# matrix4x4-b.net
KiCad netlist of a schematic drawn in EAGLE
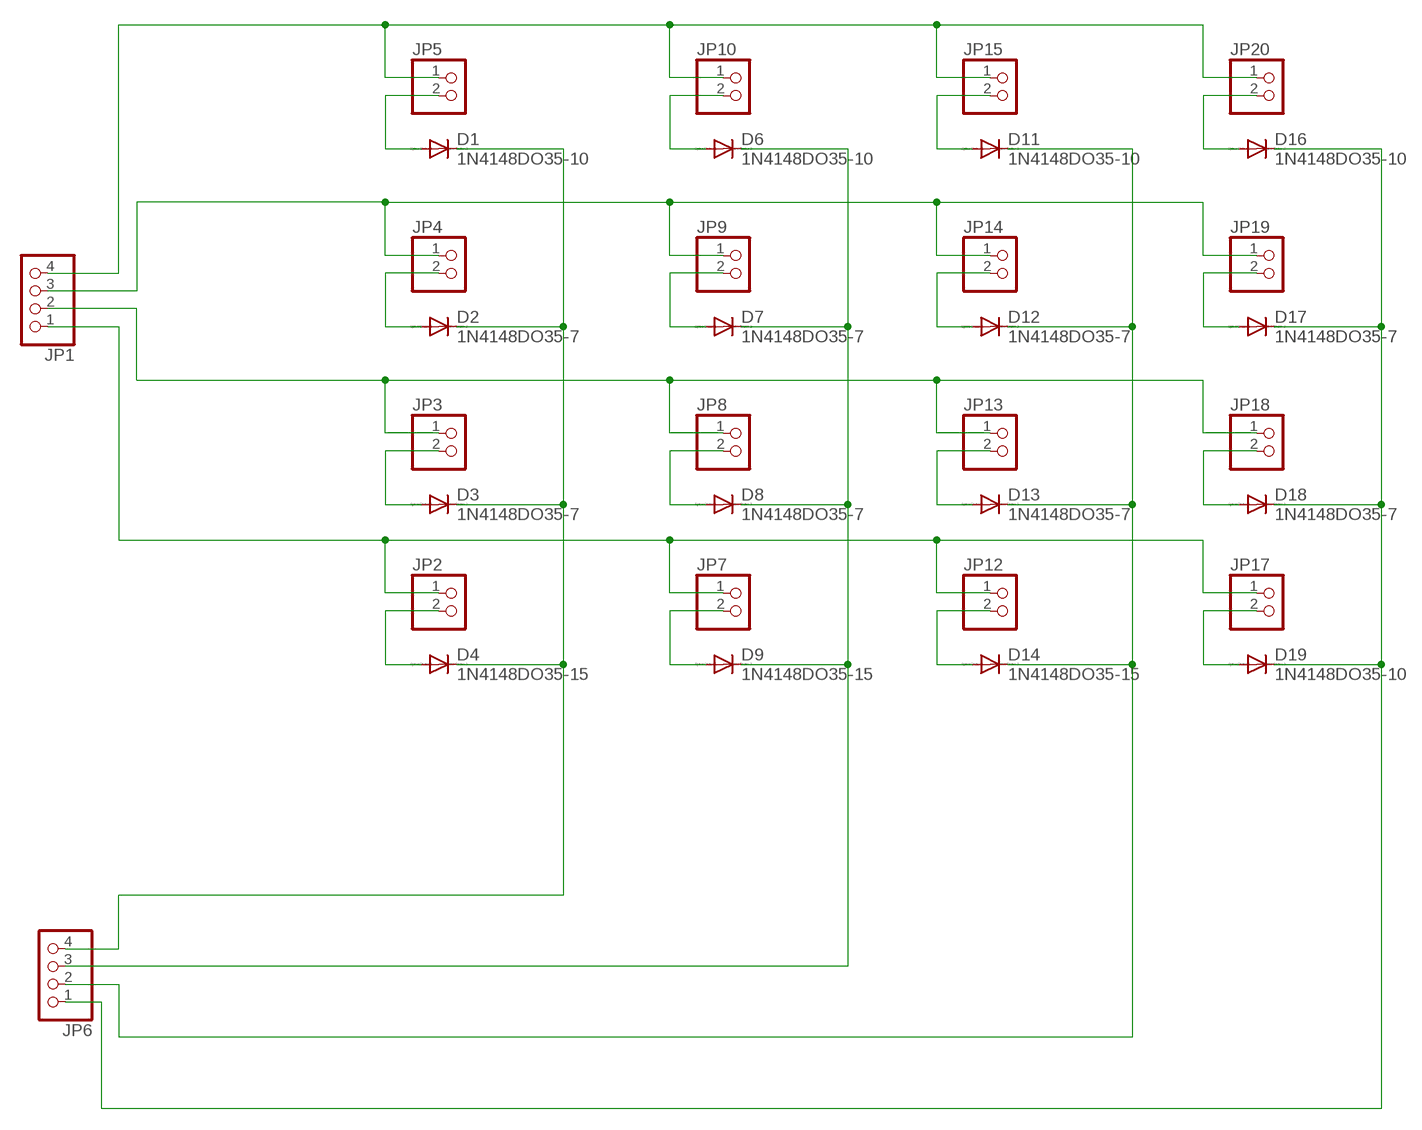
[diagram p0: schematic, sheet 1]

(export (version "E")
  (design (tool "Eeschema 10.0.6"))
  (components
    (comp (ref "D1")
      (value "1N4148DO35-10")
      (footprint "eagle-import:DO35-10")
      (libsource (lib "eagle-import") (part "diode_1N4148DO35-10"))
    )
    (comp (ref "D2")
      (value "1N4148DO35-7")
      (footprint "eagle-import:DO35-7")
      (libsource (lib "eagle-import") (part "diode_1N4148DO35-7"))
    )
    (comp (ref "D3")
      (value "1N4148DO35-7")
      (footprint "eagle-import:DO35-7")
      (libsource (lib "eagle-import") (part "diode_1N4148DO35-7"))
    )
    (comp (ref "D4")
      (value "1N4148DO35-15")
      (footprint "eagle-import:DO35-10")
      (libsource (lib "eagle-import") (part "1N4148DO35-15"))
    )
    (comp (ref "D6")
      (value "1N4148DO35-10")
      (footprint "eagle-import:DO35-10")
      (libsource (lib "eagle-import") (part "diode_1N4148DO35-10"))
    )
    (comp (ref "D7")
      (value "1N4148DO35-7")
      (footprint "eagle-import:DO35-7")
      (libsource (lib "eagle-import") (part "diode_1N4148DO35-7"))
    )
    (comp (ref "D8")
      (value "1N4148DO35-7")
      (footprint "eagle-import:DO35-7")
      (libsource (lib "eagle-import") (part "diode_1N4148DO35-7"))
    )
    (comp (ref "D9")
      (value "1N4148DO35-15")
      (footprint "eagle-import:DO35-10")
      (libsource (lib "eagle-import") (part "1N4148DO35-15"))
    )
    (comp (ref "D11")
      (value "1N4148DO35-10")
      (footprint "eagle-import:DO35-10")
      (libsource (lib "eagle-import") (part "diode_1N4148DO35-10"))
    )
    (comp (ref "D12")
      (value "1N4148DO35-7")
      (footprint "eagle-import:DO35-7")
      (libsource (lib "eagle-import") (part "diode_1N4148DO35-7"))
    )
    (comp (ref "D13")
      (value "1N4148DO35-7")
      (footprint "eagle-import:DO35-7")
      (libsource (lib "eagle-import") (part "diode_1N4148DO35-7"))
    )
    (comp (ref "D14")
      (value "1N4148DO35-15")
      (footprint "eagle-import:DO35-10")
      (libsource (lib "eagle-import") (part "1N4148DO35-15"))
    )
    (comp (ref "D16")
      (value "1N4148DO35-10")
      (footprint "eagle-import:DO35-10")
      (libsource (lib "eagle-import") (part "diode_1N4148DO35-10"))
    )
    (comp (ref "D17")
      (value "1N4148DO35-7")
      (footprint "eagle-import:DO35-7")
      (libsource (lib "eagle-import") (part "diode_1N4148DO35-7"))
    )
    (comp (ref "D18")
      (value "1N4148DO35-7")
      (footprint "eagle-import:DO35-7")
      (libsource (lib "eagle-import") (part "diode_1N4148DO35-7"))
    )
    (comp (ref "D19")
      (value "1N4148DO35-10")
      (footprint "eagle-import:DO35-10")
      (libsource (lib "eagle-import") (part "diode_1N4148DO35-10"))
    )
    (comp (ref "JP1")
      (value "PINHD-1X4")
      (footprint "eagle-import:1X04")
      (libsource (lib "eagle-import") (part "PINHD-1X4"))
    )
    (comp (ref "JP2")
      (value "PINHD-1X2")
      (footprint "eagle-import:1X02")
      (libsource (lib "eagle-import") (part "PINHD-1X2"))
    )
    (comp (ref "JP3")
      (value "PINHD-1X2")
      (footprint "eagle-import:1X02")
      (libsource (lib "eagle-import") (part "PINHD-1X2"))
    )
    (comp (ref "JP4")
      (value "PINHD-1X2")
      (footprint "eagle-import:1X02")
      (libsource (lib "eagle-import") (part "PINHD-1X2"))
    )
    (comp (ref "JP5")
      (value "PINHD-1X2")
      (footprint "eagle-import:1X02")
      (libsource (lib "eagle-import") (part "PINHD-1X2"))
    )
    (comp (ref "JP6")
      (value "PINHD-1X4")
      (footprint "eagle-import:1X04")
      (libsource (lib "eagle-import") (part "PINHD-1X4"))
    )
    (comp (ref "JP7")
      (value "PINHD-1X2")
      (footprint "eagle-import:1X02")
      (libsource (lib "eagle-import") (part "PINHD-1X2"))
    )
    (comp (ref "JP8")
      (value "PINHD-1X2")
      (footprint "eagle-import:1X02")
      (libsource (lib "eagle-import") (part "PINHD-1X2"))
    )
    (comp (ref "JP9")
      (value "PINHD-1X2")
      (footprint "eagle-import:1X02")
      (libsource (lib "eagle-import") (part "PINHD-1X2"))
    )
    (comp (ref "JP10")
      (value "PINHD-1X2")
      (footprint "eagle-import:1X02")
      (libsource (lib "eagle-import") (part "PINHD-1X2"))
    )
    (comp (ref "JP12")
      (value "PINHD-1X2")
      (footprint "eagle-import:1X02")
      (libsource (lib "eagle-import") (part "PINHD-1X2"))
    )
    (comp (ref "JP13")
      (value "PINHD-1X2")
      (footprint "eagle-import:1X02")
      (libsource (lib "eagle-import") (part "PINHD-1X2"))
    )
    (comp (ref "JP14")
      (value "PINHD-1X2")
      (footprint "eagle-import:1X02")
      (libsource (lib "eagle-import") (part "PINHD-1X2"))
    )
    (comp (ref "JP15")
      (value "PINHD-1X2")
      (footprint "eagle-import:1X02")
      (libsource (lib "eagle-import") (part "PINHD-1X2"))
    )
    (comp (ref "JP17")
      (value "PINHD-1X2")
      (footprint "eagle-import:1X02")
      (libsource (lib "eagle-import") (part "PINHD-1X2"))
    )
    (comp (ref "JP18")
      (value "PINHD-1X2")
      (footprint "eagle-import:1X02")
      (libsource (lib "eagle-import") (part "PINHD-1X2"))
    )
    (comp (ref "JP19")
      (value "PINHD-1X2")
      (footprint "eagle-import:1X02")
      (libsource (lib "eagle-import") (part "PINHD-1X2"))
    )
    (comp (ref "JP20")
      (value "PINHD-1X2")
      (footprint "eagle-import:1X02")
      (libsource (lib "eagle-import") (part "PINHD-1X2"))
    )
  )
  (nets
    (net (code "1") (name "Net-(D1-PadA)") (class "Default")
      (node (ref "D1") (pin "A") (pinfunction "A_A") (pintype "passive"))
      (node (ref "JP5") (pin "2") (pinfunction "2_2") (pintype "passive"))
    )
    (net (code "2") (name "Net-(D1-PadC)") (class "Default")
      (node (ref "D1") (pin "C") (pinfunction "C_C") (pintype "passive"))
      (node (ref "D2") (pin "C") (pinfunction "C_C") (pintype "passive"))
      (node (ref "D3") (pin "C") (pinfunction "C_C") (pintype "passive"))
      (node (ref "D4") (pin "C") (pinfunction "C_C") (pintype "passive"))
      (node (ref "JP6") (pin "4") (pinfunction "4_4") (pintype "passive"))
    )
    (net (code "3") (name "Net-(D2-PadA)") (class "Default")
      (node (ref "D2") (pin "A") (pinfunction "A_A") (pintype "passive"))
      (node (ref "JP4") (pin "2") (pinfunction "2_2") (pintype "passive"))
    )
    (net (code "4") (name "Net-(D3-PadA)") (class "Default")
      (node (ref "D3") (pin "A") (pinfunction "A_A") (pintype "passive"))
      (node (ref "JP3") (pin "2") (pinfunction "2_2") (pintype "passive"))
    )
    (net (code "5") (name "Net-(D4-PadA)") (class "Default")
      (node (ref "D4") (pin "A") (pinfunction "A_A") (pintype "passive"))
      (node (ref "JP2") (pin "2") (pinfunction "2_2") (pintype "passive"))
    )
    (net (code "6") (name "Net-(D6-PadA)") (class "Default")
      (node (ref "D6") (pin "A") (pinfunction "A_A") (pintype "passive"))
      (node (ref "JP10") (pin "2") (pinfunction "2_2") (pintype "passive"))
    )
    (net (code "7") (name "Net-(D6-PadC)") (class "Default")
      (node (ref "D6") (pin "C") (pinfunction "C_C") (pintype "passive"))
      (node (ref "D7") (pin "C") (pinfunction "C_C") (pintype "passive"))
      (node (ref "D8") (pin "C") (pinfunction "C_C") (pintype "passive"))
      (node (ref "D9") (pin "C") (pinfunction "C_C") (pintype "passive"))
      (node (ref "JP6") (pin "3") (pinfunction "3_3") (pintype "passive"))
    )
    (net (code "8") (name "Net-(D7-PadA)") (class "Default")
      (node (ref "D7") (pin "A") (pinfunction "A_A") (pintype "passive"))
      (node (ref "JP9") (pin "2") (pinfunction "2_2") (pintype "passive"))
    )
    (net (code "9") (name "Net-(D8-PadA)") (class "Default")
      (node (ref "D8") (pin "A") (pinfunction "A_A") (pintype "passive"))
      (node (ref "JP8") (pin "2") (pinfunction "2_2") (pintype "passive"))
    )
    (net (code "10") (name "Net-(D9-PadA)") (class "Default")
      (node (ref "D9") (pin "A") (pinfunction "A_A") (pintype "passive"))
      (node (ref "JP7") (pin "2") (pinfunction "2_2") (pintype "passive"))
    )
    (net (code "11") (name "Net-(D11-PadA)") (class "Default")
      (node (ref "D11") (pin "A") (pinfunction "A_A") (pintype "passive"))
      (node (ref "JP15") (pin "2") (pinfunction "2_2") (pintype "passive"))
    )
    (net (code "12") (name "Net-(D11-PadC)") (class "Default")
      (node (ref "D11") (pin "C") (pinfunction "C_C") (pintype "passive"))
      (node (ref "D12") (pin "C") (pinfunction "C_C") (pintype "passive"))
      (node (ref "D13") (pin "C") (pinfunction "C_C") (pintype "passive"))
      (node (ref "D14") (pin "C") (pinfunction "C_C") (pintype "passive"))
      (node (ref "JP6") (pin "2") (pinfunction "2_2") (pintype "passive"))
    )
    (net (code "13") (name "Net-(D12-PadA)") (class "Default")
      (node (ref "D12") (pin "A") (pinfunction "A_A") (pintype "passive"))
      (node (ref "JP14") (pin "2") (pinfunction "2_2") (pintype "passive"))
    )
    (net (code "14") (name "Net-(D13-PadA)") (class "Default")
      (node (ref "D13") (pin "A") (pinfunction "A_A") (pintype "passive"))
      (node (ref "JP13") (pin "2") (pinfunction "2_2") (pintype "passive"))
    )
    (net (code "15") (name "Net-(D14-PadA)") (class "Default")
      (node (ref "D14") (pin "A") (pinfunction "A_A") (pintype "passive"))
      (node (ref "JP12") (pin "2") (pinfunction "2_2") (pintype "passive"))
    )
    (net (code "16") (name "Net-(D16-PadA)") (class "Default")
      (node (ref "D16") (pin "A") (pinfunction "A_A") (pintype "passive"))
      (node (ref "JP20") (pin "2") (pinfunction "2_2") (pintype "passive"))
    )
    (net (code "17") (name "Net-(D16-PadC)") (class "Default")
      (node (ref "D16") (pin "C") (pinfunction "C_C") (pintype "passive"))
      (node (ref "D17") (pin "C") (pinfunction "C_C") (pintype "passive"))
      (node (ref "D18") (pin "C") (pinfunction "C_C") (pintype "passive"))
      (node (ref "D19") (pin "C") (pinfunction "C_C") (pintype "passive"))
      (node (ref "JP6") (pin "1") (pinfunction "1_1") (pintype "passive"))
    )
    (net (code "18") (name "Net-(D17-PadA)") (class "Default")
      (node (ref "D17") (pin "A") (pinfunction "A_A") (pintype "passive"))
      (node (ref "JP19") (pin "2") (pinfunction "2_2") (pintype "passive"))
    )
    (net (code "19") (name "Net-(D18-PadA)") (class "Default")
      (node (ref "D18") (pin "A") (pinfunction "A_A") (pintype "passive"))
      (node (ref "JP18") (pin "2") (pinfunction "2_2") (pintype "passive"))
    )
    (net (code "20") (name "Net-(D19-PadA)") (class "Default")
      (node (ref "D19") (pin "A") (pinfunction "A_A") (pintype "passive"))
      (node (ref "JP17") (pin "2") (pinfunction "2_2") (pintype "passive"))
    )
    (net (code "21") (name "Net-(JP1-Pad1)") (class "Default")
      (node (ref "JP1") (pin "1") (pinfunction "1_1") (pintype "passive"))
      (node (ref "JP12") (pin "1") (pinfunction "1_1") (pintype "passive"))
      (node (ref "JP17") (pin "1") (pinfunction "1_1") (pintype "passive"))
      (node (ref "JP2") (pin "1") (pinfunction "1_1") (pintype "passive"))
      (node (ref "JP7") (pin "1") (pinfunction "1_1") (pintype "passive"))
    )
    (net (code "22") (name "Net-(JP1-Pad2)") (class "Default")
      (node (ref "JP1") (pin "2") (pinfunction "2_2") (pintype "passive"))
      (node (ref "JP13") (pin "1") (pinfunction "1_1") (pintype "passive"))
      (node (ref "JP18") (pin "1") (pinfunction "1_1") (pintype "passive"))
      (node (ref "JP3") (pin "1") (pinfunction "1_1") (pintype "passive"))
      (node (ref "JP8") (pin "1") (pinfunction "1_1") (pintype "passive"))
    )
    (net (code "23") (name "Net-(JP1-Pad3)") (class "Default")
      (node (ref "JP1") (pin "3") (pinfunction "3_3") (pintype "passive"))
      (node (ref "JP14") (pin "1") (pinfunction "1_1") (pintype "passive"))
      (node (ref "JP19") (pin "1") (pinfunction "1_1") (pintype "passive"))
      (node (ref "JP4") (pin "1") (pinfunction "1_1") (pintype "passive"))
      (node (ref "JP9") (pin "1") (pinfunction "1_1") (pintype "passive"))
    )
    (net (code "24") (name "Net-(JP1-Pad4)") (class "Default")
      (node (ref "JP1") (pin "4") (pinfunction "4_4") (pintype "passive"))
      (node (ref "JP10") (pin "1") (pinfunction "1_1") (pintype "passive"))
      (node (ref "JP15") (pin "1") (pinfunction "1_1") (pintype "passive"))
      (node (ref "JP20") (pin "1") (pinfunction "1_1") (pintype "passive"))
      (node (ref "JP5") (pin "1") (pinfunction "1_1") (pintype "passive"))
    )
  )
)
